# STM32_MCU.net
KiCad netlist of a schematic drawn in Altium Designer
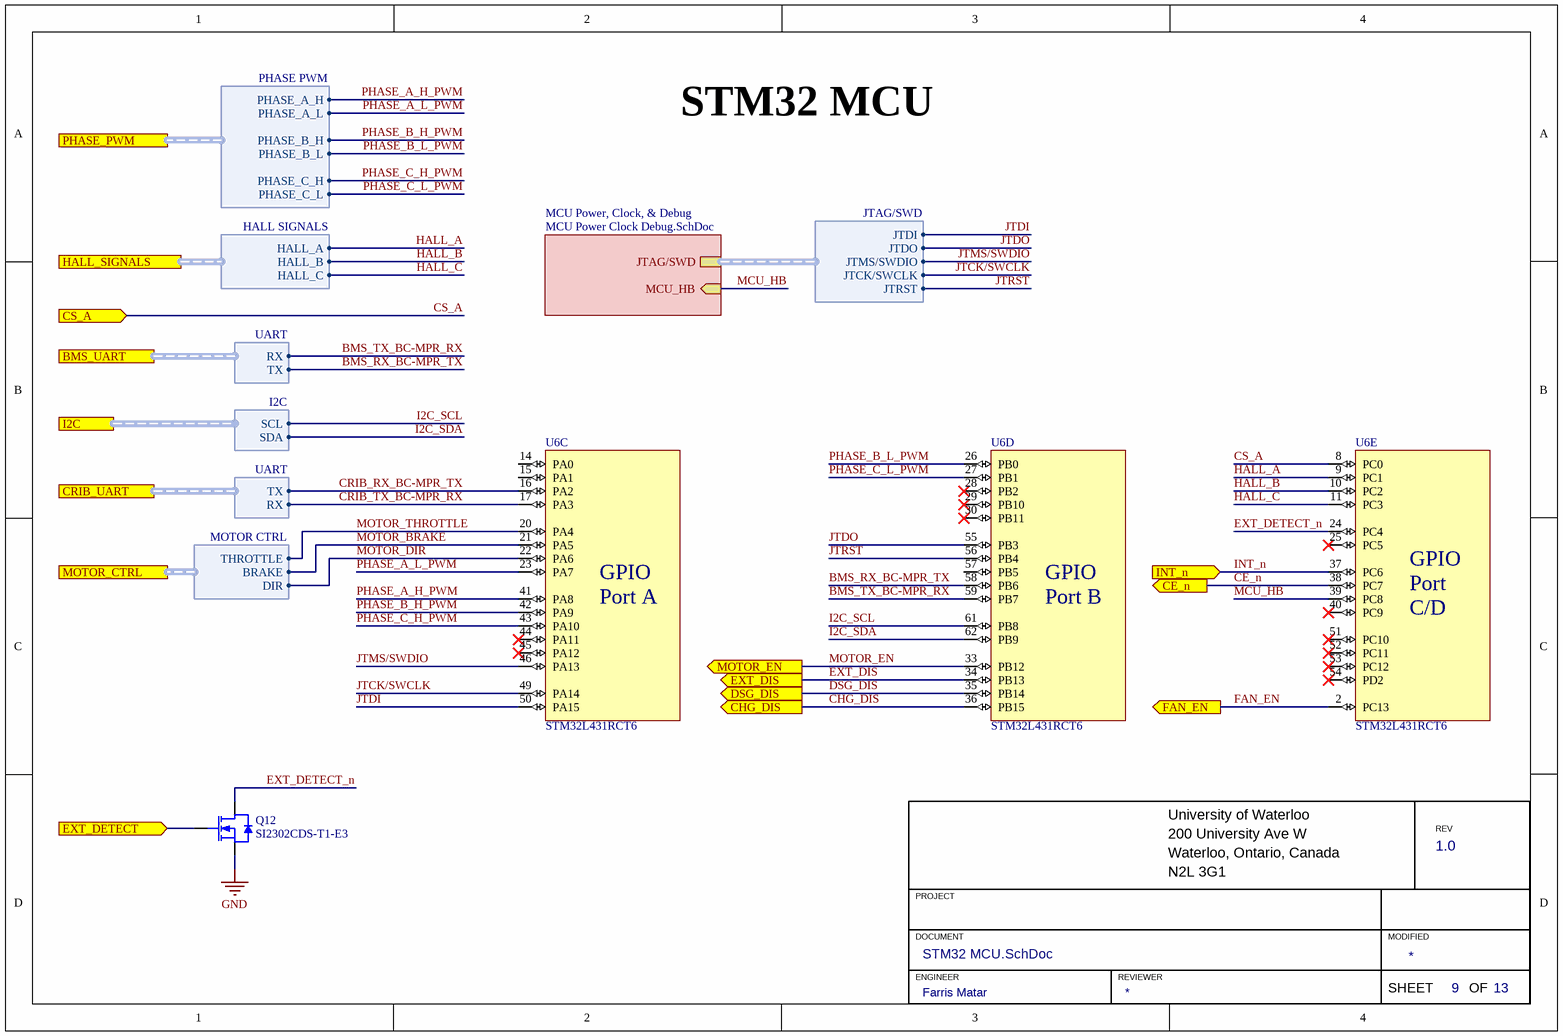
[diagram p0: STM32 MCU.SchDoc]

(export (version "E")
  (design (tool "Eeschema 10.0.6"))
  (components
    (comp (ref "Q12")
      (value "NMOS_20V_6A")
      (footprint "SOT23-3")
      (description "MOSFET N-CH 20V 2.6A SOT23-3")
      (fields (field (name "MANUFACTURER PART NUMBER 1") "SI2302CDS-T1-E3"))
      (libsource (lib "Personal_Schematic_Library_2022") (part "NMOS_20V_2.6A"))
    )
    (comp (ref "U6")
      (value "STM32L431RCT6")
      (footprint "STM_LQFP64")
      (description "IC MCU 32BIT 256KB FLASH 64LQFP")
      (libsource (lib "") (part "STM32L431RCT6_1"))
    )
  )
  (nets
    (net (code "10") (name "/BMS_RX_BC-MPR_TX") (class "Default")
      (node (ref "U6") (pin "58") (pinfunction "PB6_58") (pintype "bidirectional"))
    )
    (net (code "11") (name "/BMS_TX_BC-MPR_RX") (class "Default")
      (node (ref "U6") (pin "59") (pinfunction "PB7_59") (pintype "bidirectional"))
    )
    (net (code "12") (name "/CE_n") (class "Default")
      (node (ref "U6") (pin "38") (pinfunction "PC7_38") (pintype "bidirectional"))
    )
    (net (code "13") (name "/CHG_DIS") (class "Default")
      (node (ref "U6") (pin "36") (pinfunction "PB15_36") (pintype "bidirectional"))
    )
    (net (code "14") (name "/CRIB_RX_BC-MPR_TX") (class "Default")
      (node (ref "U6") (pin "16") (pinfunction "PA2_16") (pintype "bidirectional"))
    )
    (net (code "15") (name "/CRIB_TX_BC-MPR_RX") (class "Default")
      (node (ref "U6") (pin "17") (pinfunction "PA3_17") (pintype "bidirectional"))
    )
    (net (code "16") (name "/CS_A") (class "Default")
      (node (ref "U6") (pin "8") (pinfunction "PC0_8") (pintype "bidirectional"))
    )
    (net (code "17") (name "/DSG_DIS") (class "Default")
      (node (ref "U6") (pin "35") (pinfunction "PB14_35") (pintype "bidirectional"))
    )
    (net (code "18") (name "/EXT_DETECT") (class "Default")
      (node (ref "Q12") (pin "1") (pinfunction "GATE_1") (pintype "passive"))
    )
    (net (code "19") (name "/EXT_DETECT_n") (class "Default")
      (node (ref "Q12") (pin "3") (pinfunction "DRAIN_3") (pintype "passive"))
      (node (ref "U6") (pin "24") (pinfunction "PC4_24") (pintype "bidirectional"))
    )
    (net (code "20") (name "/EXT_DIS") (class "Default")
      (node (ref "U6") (pin "34") (pinfunction "PB13_34") (pintype "bidirectional"))
    )
    (net (code "21") (name "/FAN_EN") (class "Default")
      (node (ref "U6") (pin "2") (pinfunction "PC13_2") (pintype "bidirectional"))
    )
    (net (code "22") (name "/HALL_A") (class "Default")
      (node (ref "U6") (pin "9") (pinfunction "PC1_9") (pintype "bidirectional"))
    )
    (net (code "23") (name "/HALL_B") (class "Default")
      (node (ref "U6") (pin "10") (pinfunction "PC2_10") (pintype "bidirectional"))
    )
    (net (code "24") (name "/HALL_C") (class "Default")
      (node (ref "U6") (pin "11") (pinfunction "PC3_11") (pintype "bidirectional"))
    )
    (net (code "25") (name "/I2C_SCL") (class "Default")
      (node (ref "U6") (pin "61") (pinfunction "PB8_61") (pintype "bidirectional"))
    )
    (net (code "26") (name "/I2C_SDA") (class "Default")
      (node (ref "U6") (pin "62") (pinfunction "PB9_62") (pintype "bidirectional"))
    )
    (net (code "27") (name "/INT_n") (class "Default")
      (node (ref "U6") (pin "37") (pinfunction "PC6_37") (pintype "bidirectional"))
    )
    (net (code "28") (name "/JTCK{slash}SWCLK") (class "Default")
      (node (ref "U6") (pin "49") (pinfunction "PA14_49") (pintype "bidirectional"))
    )
    (net (code "29") (name "/JTDI") (class "Default")
      (node (ref "U6") (pin "50") (pinfunction "PA15_50") (pintype "bidirectional"))
    )
    (net (code "30") (name "/JTDO") (class "Default")
      (node (ref "U6") (pin "55") (pinfunction "PB3_55") (pintype "bidirectional"))
    )
    (net (code "31") (name "/JTMS{slash}SWDIO") (class "Default")
      (node (ref "U6") (pin "46") (pinfunction "PA13_46") (pintype "bidirectional"))
    )
    (net (code "32") (name "/JTRST") (class "Default")
      (node (ref "U6") (pin "56") (pinfunction "PB4_56") (pintype "bidirectional"))
    )
    (net (code "33") (name "/MCU_HB") (class "Default")
      (node (ref "U6") (pin "39") (pinfunction "PC8_39") (pintype "bidirectional"))
    )
    (net (code "34") (name "/MOTOR_BRAKE") (class "Default")
      (node (ref "U6") (pin "21") (pinfunction "PA5_21") (pintype "bidirectional"))
    )
    (net (code "35") (name "/MOTOR_DIR") (class "Default")
      (node (ref "U6") (pin "22") (pinfunction "PA6_22") (pintype "bidirectional"))
    )
    (net (code "36") (name "/MOTOR_EN") (class "Default")
      (node (ref "U6") (pin "33") (pinfunction "PB12_33") (pintype "bidirectional"))
    )
    (net (code "37") (name "/MOTOR_THROTTLE") (class "Default")
      (node (ref "U6") (pin "20") (pinfunction "PA4_20") (pintype "bidirectional"))
    )
    (net (code "38") (name "/PHASE_A_H_PWM") (class "Default")
      (node (ref "U6") (pin "41") (pinfunction "PA8_41") (pintype "bidirectional"))
    )
    (net (code "39") (name "/PHASE_A_L_PWM") (class "Default")
      (node (ref "U6") (pin "23") (pinfunction "PA7_23") (pintype "bidirectional"))
    )
    (net (code "40") (name "/PHASE_B_H_PWM") (class "Default")
      (node (ref "U6") (pin "42") (pinfunction "PA9_42") (pintype "bidirectional"))
    )
    (net (code "41") (name "/PHASE_B_L_PWM") (class "Default")
      (node (ref "U6") (pin "26") (pinfunction "PB0_26") (pintype "bidirectional"))
    )
    (net (code "42") (name "/PHASE_C_H_PWM") (class "Default")
      (node (ref "U6") (pin "43") (pinfunction "PA10_43") (pintype "bidirectional"))
    )
    (net (code "43") (name "/PHASE_C_L_PWM") (class "Default")
      (node (ref "U6") (pin "27") (pinfunction "PB1_27") (pintype "bidirectional"))
    )
    (net (code "50") (name "GND") (class "Default")
      (node (ref "Q12") (pin "2") (pinfunction "SOURCE_2") (pintype "passive"))
    )
    (net (code "51") (name "unconnected-(U6C-PA0-Pad14)") (class "Default")
      (node (ref "U6") (pin "14") (pinfunction "PA0_14") (pintype "bidirectional"))
    )
    (net (code "52") (name "unconnected-(U6C-PA1-Pad15)") (class "Default")
      (node (ref "U6") (pin "15") (pinfunction "PA1_15") (pintype "bidirectional"))
    )
    (net (code "53") (name "unconnected-(U6C-PA11-Pad44)") (class "Default")
      (node (ref "U6") (pin "44") (pinfunction "PA11_44") (pintype "bidirectional+no_connect"))
    )
    (net (code "54") (name "unconnected-(U6C-PA12-Pad45)") (class "Default")
      (node (ref "U6") (pin "45") (pinfunction "PA12_45") (pintype "bidirectional+no_connect"))
    )
    (net (code "55") (name "unconnected-(U6D-PB2-Pad28)") (class "Default")
      (node (ref "U6") (pin "28") (pinfunction "PB2_28") (pintype "bidirectional+no_connect"))
    )
    (net (code "56") (name "unconnected-(U6D-PB5-Pad57)") (class "Default")
      (node (ref "U6") (pin "57") (pinfunction "PB5_57") (pintype "bidirectional"))
    )
    (net (code "57") (name "unconnected-(U6D-PB10-Pad29)") (class "Default")
      (node (ref "U6") (pin "29") (pinfunction "PB10_29") (pintype "bidirectional+no_connect"))
    )
    (net (code "58") (name "unconnected-(U6D-PB11-Pad30)") (class "Default")
      (node (ref "U6") (pin "30") (pinfunction "PB11_30") (pintype "bidirectional+no_connect"))
    )
    (net (code "59") (name "unconnected-(U6E-PC5-Pad25)") (class "Default")
      (node (ref "U6") (pin "25") (pinfunction "PC5_25") (pintype "bidirectional+no_connect"))
    )
    (net (code "60") (name "unconnected-(U6E-PC9-Pad40)") (class "Default")
      (node (ref "U6") (pin "40") (pinfunction "PC9_40") (pintype "bidirectional+no_connect"))
    )
    (net (code "61") (name "unconnected-(U6E-PC10-Pad51)") (class "Default")
      (node (ref "U6") (pin "51") (pinfunction "PC10_51") (pintype "bidirectional+no_connect"))
    )
    (net (code "62") (name "unconnected-(U6E-PC11-Pad52)") (class "Default")
      (node (ref "U6") (pin "52") (pinfunction "PC11_52") (pintype "bidirectional+no_connect"))
    )
    (net (code "63") (name "unconnected-(U6E-PC12-Pad53)") (class "Default")
      (node (ref "U6") (pin "53") (pinfunction "PC12_53") (pintype "bidirectional+no_connect"))
    )
    (net (code "64") (name "unconnected-(U6E-PD2-Pad54)") (class "Default")
      (node (ref "U6") (pin "54") (pinfunction "PD2_54") (pintype "bidirectional+no_connect"))
    )
  )
)
